# 07_-_INPUT.net
KiCad netlist of a schematic drawn in Altium Designer
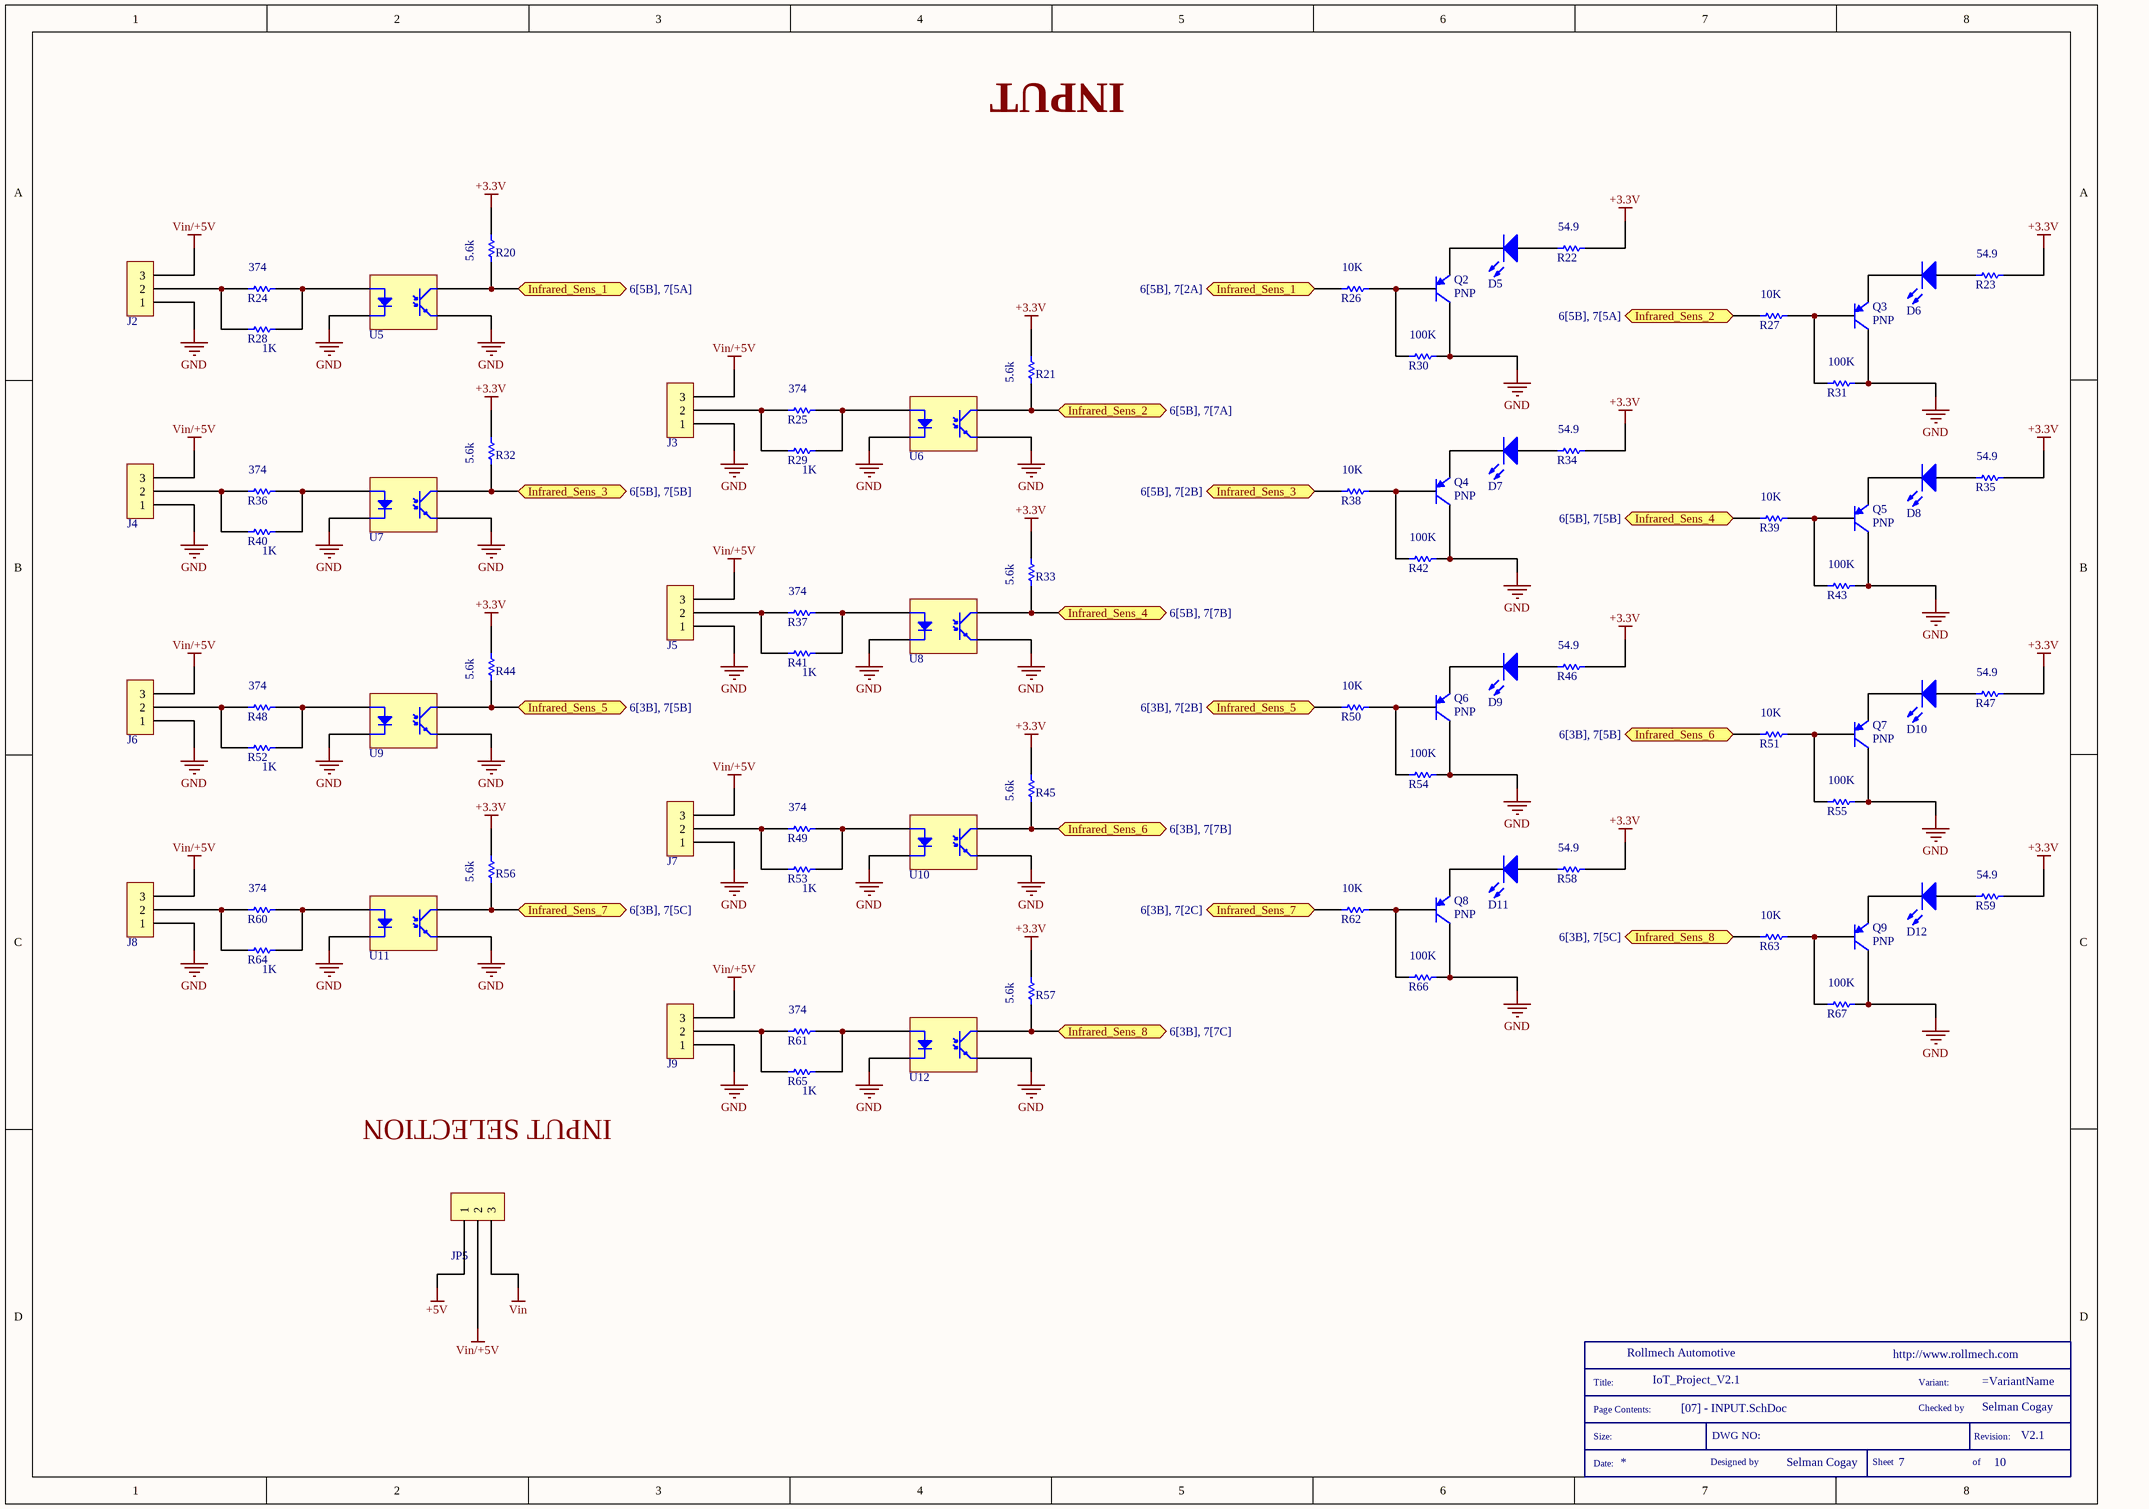
[diagram p0: [07] - INPUT.SchDoc]

(export (version "E")
  (design (tool "Eeschema 10.0.6"))
  (components
    (comp (ref "D5")
      (value "Blue Led")
      (footprint "RES_0603")
      (description "LED BLUE CLEAR 2SMD")
      (libsource (lib "Rollmech_Altium") (part "EAST16084BA8"))
    )
    (comp (ref "D6")
      (value "Blue Led")
      (footprint "RES_0603")
      (description "LED BLUE CLEAR 2SMD")
      (libsource (lib "Rollmech_Altium") (part "EAST16084BA8"))
    )
    (comp (ref "D7")
      (value "Blue Led")
      (footprint "RES_0603")
      (description "LED BLUE CLEAR 2SMD")
      (libsource (lib "Rollmech_Altium") (part "EAST16084BA8"))
    )
    (comp (ref "D8")
      (value "Blue Led")
      (footprint "RES_0603")
      (description "LED BLUE CLEAR 2SMD")
      (libsource (lib "Rollmech_Altium") (part "EAST16084BA8"))
    )
    (comp (ref "D9")
      (value "Blue Led")
      (footprint "RES_0603")
      (description "LED BLUE CLEAR 2SMD")
      (libsource (lib "Rollmech_Altium") (part "EAST16084BA8"))
    )
    (comp (ref "D10")
      (value "Blue Led")
      (footprint "RES_0603")
      (description "LED BLUE CLEAR 2SMD")
      (libsource (lib "Rollmech_Altium") (part "EAST16084BA8"))
    )
    (comp (ref "D11")
      (value "Blue Led")
      (footprint "RES_0603")
      (description "LED BLUE CLEAR 2SMD")
      (libsource (lib "Rollmech_Altium") (part "EAST16084BA8"))
    )
    (comp (ref "D12")
      (value "Blue Led")
      (footprint "RES_0603")
      (description "LED BLUE CLEAR 2SMD")
      (libsource (lib "Rollmech_Altium") (part "EAST16084BA8"))
    )
    (comp (ref "J2")
      (value "CONN 1X3 3MM")
      (footprint "CONN_MALE_1X3_3MM")
      (description "CONN MALE 1X3 3MM")
      (libsource (lib "Rollmech_Altium") (part "66200311122"))
    )
    (comp (ref "J3")
      (value "CONN 1X3 3MM")
      (footprint "CONN_MALE_1X3_3MM")
      (description "CONN MALE 1X3 3MM")
      (libsource (lib "Rollmech_Altium") (part "66200311122"))
    )
    (comp (ref "J4")
      (value "CONN 1X3 3MM")
      (footprint "CONN_MALE_1X3_3MM")
      (description "CONN MALE 1X3 3MM")
      (libsource (lib "Rollmech_Altium") (part "66200311122"))
    )
    (comp (ref "J5")
      (value "CONN 1X3 3MM")
      (footprint "CONN_MALE_1X3_3MM")
      (description "CONN MALE 1X3 3MM")
      (libsource (lib "Rollmech_Altium") (part "66200311122"))
    )
    (comp (ref "J6")
      (value "CONN 1X3 3MM")
      (footprint "CONN_MALE_1X3_3MM")
      (description "CONN MALE 1X3 3MM")
      (libsource (lib "Rollmech_Altium") (part "66200311122"))
    )
    (comp (ref "J7")
      (value "CONN 1X3 3MM")
      (footprint "CONN_MALE_1X3_3MM")
      (description "CONN MALE 1X3 3MM")
      (libsource (lib "Rollmech_Altium") (part "66200311122"))
    )
    (comp (ref "J8")
      (value "CONN 1X3 3MM")
      (footprint "CONN_MALE_1X3_3MM")
      (description "CONN MALE 1X3 3MM")
      (libsource (lib "Rollmech_Altium") (part "66200311122"))
    )
    (comp (ref "J9")
      (value "CONN 1X3 3MM")
      (footprint "CONN_MALE_1X3_3MM")
      (description "CONN MALE 1X3 3MM")
      (libsource (lib "Rollmech_Altium") (part "66200311122"))
    )
    (comp (ref "JP5")
      (value "HDR_1X3_2.54")
      (footprint "HDR_MALE_1X3_2.54MM")
      (description "HDR MALE 1X3 2.54MM")
      (libsource (lib "Rollmech_Altium") (part "61300311121"))
    )
    (comp (ref "Q2")
      (value "PNP")
      (footprint "SOT-23 (TO-236)")
      (description "TRANS PNP 60V 0.6A SOT23-3")
      (libsource (lib "Rollmech_Altium") (part "MMBT2907A-7-F"))
    )
    (comp (ref "Q3")
      (value "PNP")
      (footprint "SOT-23 (TO-236)")
      (description "TRANS PNP 60V 0.6A SOT23-3")
      (libsource (lib "Rollmech_Altium") (part "MMBT2907A-7-F"))
    )
    (comp (ref "Q4")
      (value "PNP")
      (footprint "SOT-23 (TO-236)")
      (description "TRANS PNP 60V 0.6A SOT23-3")
      (libsource (lib "Rollmech_Altium") (part "MMBT2907A-7-F"))
    )
    (comp (ref "Q5")
      (value "PNP")
      (footprint "SOT-23 (TO-236)")
      (description "TRANS PNP 60V 0.6A SOT23-3")
      (libsource (lib "Rollmech_Altium") (part "MMBT2907A-7-F"))
    )
    (comp (ref "Q6")
      (value "PNP")
      (footprint "SOT-23 (TO-236)")
      (description "TRANS PNP 60V 0.6A SOT23-3")
      (libsource (lib "Rollmech_Altium") (part "MMBT2907A-7-F"))
    )
    (comp (ref "Q7")
      (value "PNP")
      (footprint "SOT-23 (TO-236)")
      (description "TRANS PNP 60V 0.6A SOT23-3")
      (libsource (lib "Rollmech_Altium") (part "MMBT2907A-7-F"))
    )
    (comp (ref "Q8")
      (value "PNP")
      (footprint "SOT-23 (TO-236)")
      (description "TRANS PNP 60V 0.6A SOT23-3")
      (libsource (lib "Rollmech_Altium") (part "MMBT2907A-7-F"))
    )
    (comp (ref "Q9")
      (value "PNP")
      (footprint "SOT-23 (TO-236)")
      (description "TRANS PNP 60V 0.6A SOT23-3")
      (libsource (lib "Rollmech_Altium") (part "MMBT2907A-7-F"))
    )
    (comp (ref "R20")
      (value "5.6k")
      (footprint "RES_0805")
      (description "RES SMD 5.6K OHM 1% 1/8W 0805")
      (libsource (lib "Rollmech_Altium") (part "ERJ-6ENF5601V"))
    )
    (comp (ref "R21")
      (value "5.6k")
      (footprint "RES_0805")
      (description "RES SMD 5.6K OHM 1% 1/8W 0805")
      (libsource (lib "Rollmech_Altium") (part "ERJ-6ENF5601V"))
    )
    (comp (ref "R22")
      (value "54.9")
      (footprint "RES_0805")
      (description "RES SMD 54.9 OHM")
      (libsource (lib "Rollmech_Altium") (part "ERJ-6ENF54R9V"))
    )
    (comp (ref "R23")
      (value "54.9")
      (footprint "RES_0805")
      (description "RES SMD 54.9 OHM")
      (libsource (lib "Rollmech_Altium") (part "ERJ-6ENF54R9V"))
    )
    (comp (ref "R24")
      (value "374")
      (footprint "RES_0805")
      (description "RES SMD 374 OHM 1% 1/8W 0805")
      (libsource (lib "Rollmech_Altium") (part "ERJ-6ENF3740V"))
    )
    (comp (ref "R25")
      (value "374")
      (footprint "RES_0805")
      (description "RES SMD 374 OHM 1% 1/8W 0805")
      (libsource (lib "Rollmech_Altium") (part "ERJ-6ENF3740V"))
    )
    (comp (ref "R26")
      (value "10K")
      (footprint "RES_0805")
      (description "RES SMD 10K OHM 1% 1/8W 0805")
      (libsource (lib "Rollmech_Altium") (part "ERJ-6ENF1002V"))
    )
    (comp (ref "R27")
      (value "10K")
      (footprint "RES_0805")
      (description "RES SMD 10K OHM 1% 1/8W 0805")
      (libsource (lib "Rollmech_Altium") (part "ERJ-6ENF1002V"))
    )
    (comp (ref "R28")
      (value "1K")
      (footprint "RES_0805")
      (description "RES SMD 1K OHM")
      (libsource (lib "Rollmech_Altium") (part "ERJ-6ENF1001V"))
    )
    (comp (ref "R29")
      (value "1K")
      (footprint "RES_0805")
      (description "RES SMD 1K OHM")
      (libsource (lib "Rollmech_Altium") (part "ERJ-6ENF1001V"))
    )
    (comp (ref "R30")
      (value "100K")
      (footprint "RES_0603")
      (description "RES SMD 100K 5% 1/4W 0603")
      (libsource (lib "Rollmech_Altium") (part "ERJ-PA3J104V"))
    )
    (comp (ref "R31")
      (value "100K")
      (footprint "RES_0603")
      (description "RES SMD 100K 5% 1/4W 0603")
      (libsource (lib "Rollmech_Altium") (part "ERJ-PA3J104V"))
    )
    (comp (ref "R32")
      (value "5.6k")
      (footprint "RES_0805")
      (description "RES SMD 5.6K OHM 1% 1/8W 0805")
      (libsource (lib "Rollmech_Altium") (part "ERJ-6ENF5601V"))
    )
    (comp (ref "R33")
      (value "5.6k")
      (footprint "RES_0805")
      (description "RES SMD 5.6K OHM 1% 1/8W 0805")
      (libsource (lib "Rollmech_Altium") (part "ERJ-6ENF5601V"))
    )
    (comp (ref "R34")
      (value "54.9")
      (footprint "RES_0805")
      (description "RES SMD 54.9 OHM")
      (libsource (lib "Rollmech_Altium") (part "ERJ-6ENF54R9V"))
    )
    (comp (ref "R35")
      (value "54.9")
      (footprint "RES_0805")
      (description "RES SMD 54.9 OHM")
      (libsource (lib "Rollmech_Altium") (part "ERJ-6ENF54R9V"))
    )
    (comp (ref "R36")
      (value "374")
      (footprint "RES_0805")
      (description "RES SMD 374 OHM 1% 1/8W 0805")
      (libsource (lib "Rollmech_Altium") (part "ERJ-6ENF3740V"))
    )
    (comp (ref "R37")
      (value "374")
      (footprint "RES_0805")
      (description "RES SMD 374 OHM 1% 1/8W 0805")
      (libsource (lib "Rollmech_Altium") (part "ERJ-6ENF3740V"))
    )
    (comp (ref "R38")
      (value "10K")
      (footprint "RES_0805")
      (description "RES SMD 10K OHM 1% 1/8W 0805")
      (libsource (lib "Rollmech_Altium") (part "ERJ-6ENF1002V"))
    )
    (comp (ref "R39")
      (value "10K")
      (footprint "RES_0805")
      (description "RES SMD 10K OHM 1% 1/8W 0805")
      (libsource (lib "Rollmech_Altium") (part "ERJ-6ENF1002V"))
    )
    (comp (ref "R40")
      (value "1K")
      (footprint "RES_0805")
      (description "RES SMD 1K OHM")
      (libsource (lib "Rollmech_Altium") (part "ERJ-6ENF1001V"))
    )
    (comp (ref "R41")
      (value "1K")
      (footprint "RES_0805")
      (description "RES SMD 1K OHM")
      (libsource (lib "Rollmech_Altium") (part "ERJ-6ENF1001V"))
    )
    (comp (ref "R42")
      (value "100K")
      (footprint "RES_0603")
      (description "RES SMD 100K 5% 1/4W 0603")
      (libsource (lib "Rollmech_Altium") (part "ERJ-PA3J104V"))
    )
    (comp (ref "R43")
      (value "100K")
      (footprint "RES_0603")
      (description "RES SMD 100K 5% 1/4W 0603")
      (libsource (lib "Rollmech_Altium") (part "ERJ-PA3J104V"))
    )
    (comp (ref "R44")
      (value "5.6k")
      (footprint "RES_0805")
      (description "RES SMD 5.6K OHM 1% 1/8W 0805")
      (libsource (lib "Rollmech_Altium") (part "ERJ-6ENF5601V"))
    )
    (comp (ref "R45")
      (value "5.6k")
      (footprint "RES_0805")
      (description "RES SMD 5.6K OHM 1% 1/8W 0805")
      (libsource (lib "Rollmech_Altium") (part "ERJ-6ENF5601V"))
    )
    (comp (ref "R46")
      (value "54.9")
      (footprint "RES_0805")
      (description "RES SMD 54.9 OHM")
      (libsource (lib "Rollmech_Altium") (part "ERJ-6ENF54R9V"))
    )
    (comp (ref "R47")
      (value "54.9")
      (footprint "RES_0805")
      (description "RES SMD 54.9 OHM")
      (libsource (lib "Rollmech_Altium") (part "ERJ-6ENF54R9V"))
    )
    (comp (ref "R48")
      (value "374")
      (footprint "RES_0805")
      (description "RES SMD 374 OHM 1% 1/8W 0805")
      (libsource (lib "Rollmech_Altium") (part "ERJ-6ENF3740V"))
    )
    (comp (ref "R49")
      (value "374")
      (footprint "RES_0805")
      (description "RES SMD 374 OHM 1% 1/8W 0805")
      (libsource (lib "Rollmech_Altium") (part "ERJ-6ENF3740V"))
    )
    (comp (ref "R50")
      (value "10K")
      (footprint "RES_0805")
      (description "RES SMD 10K OHM 1% 1/8W 0805")
      (libsource (lib "Rollmech_Altium") (part "ERJ-6ENF1002V"))
    )
    (comp (ref "R51")
      (value "10K")
      (footprint "RES_0805")
      (description "RES SMD 10K OHM 1% 1/8W 0805")
      (libsource (lib "Rollmech_Altium") (part "ERJ-6ENF1002V"))
    )
    (comp (ref "R52")
      (value "1K")
      (footprint "RES_0805")
      (description "RES SMD 1K OHM")
      (libsource (lib "Rollmech_Altium") (part "ERJ-6ENF1001V"))
    )
    (comp (ref "R53")
      (value "1K")
      (footprint "RES_0805")
      (description "RES SMD 1K OHM")
      (libsource (lib "Rollmech_Altium") (part "ERJ-6ENF1001V"))
    )
    (comp (ref "R54")
      (value "100K")
      (footprint "RES_0603")
      (description "RES SMD 100K 5% 1/4W 0603")
      (libsource (lib "Rollmech_Altium") (part "ERJ-PA3J104V"))
    )
    (comp (ref "R55")
      (value "100K")
      (footprint "RES_0603")
      (description "RES SMD 100K 5% 1/4W 0603")
      (libsource (lib "Rollmech_Altium") (part "ERJ-PA3J104V"))
    )
    (comp (ref "R56")
      (value "5.6k")
      (footprint "RES_0805")
      (description "RES SMD 5.6K OHM 1% 1/8W 0805")
      (libsource (lib "Rollmech_Altium") (part "ERJ-6ENF5601V"))
    )
    (comp (ref "R57")
      (value "5.6k")
      (footprint "RES_0805")
      (description "RES SMD 5.6K OHM 1% 1/8W 0805")
      (libsource (lib "Rollmech_Altium") (part "ERJ-6ENF5601V"))
    )
    (comp (ref "R58")
      (value "54.9")
      (footprint "RES_0805")
      (description "RES SMD 54.9 OHM")
      (libsource (lib "Rollmech_Altium") (part "ERJ-6ENF54R9V"))
    )
    (comp (ref "R59")
      (value "54.9")
      (footprint "RES_0805")
      (description "RES SMD 54.9 OHM")
      (libsource (lib "Rollmech_Altium") (part "ERJ-6ENF54R9V"))
    )
    (comp (ref "R60")
      (value "374")
      (footprint "RES_0805")
      (description "RES SMD 374 OHM 1% 1/8W 0805")
      (libsource (lib "Rollmech_Altium") (part "ERJ-6ENF3740V"))
    )
    (comp (ref "R61")
      (value "374")
      (footprint "RES_0805")
      (description "RES SMD 374 OHM 1% 1/8W 0805")
      (libsource (lib "Rollmech_Altium") (part "ERJ-6ENF3740V"))
    )
    (comp (ref "R62")
      (value "10K")
      (footprint "RES_0805")
      (description "RES SMD 10K OHM 1% 1/8W 0805")
      (libsource (lib "Rollmech_Altium") (part "ERJ-6ENF1002V"))
    )
    (comp (ref "R63")
      (value "10K")
      (footprint "RES_0805")
      (description "RES SMD 10K OHM 1% 1/8W 0805")
      (libsource (lib "Rollmech_Altium") (part "ERJ-6ENF1002V"))
    )
    (comp (ref "R64")
      (value "1K")
      (footprint "RES_0805")
      (description "RES SMD 1K OHM")
      (libsource (lib "Rollmech_Altium") (part "ERJ-6ENF1001V"))
    )
    (comp (ref "R65")
      (value "1K")
      (footprint "RES_0805")
      (description "RES SMD 1K OHM")
      (libsource (lib "Rollmech_Altium") (part "ERJ-6ENF1001V"))
    )
    (comp (ref "R66")
      (value "100K")
      (footprint "RES_0603")
      (description "RES SMD 100K 5% 1/4W 0603")
      (libsource (lib "Rollmech_Altium") (part "ERJ-PA3J104V"))
    )
    (comp (ref "R67")
      (value "100K")
      (footprint "RES_0603")
      (description "RES SMD 100K 5% 1/4W 0603")
      (libsource (lib "Rollmech_Altium") (part "ERJ-PA3J104V"))
    )
    (comp (ref "U5")
      (value "NPN 3.75KV")
      (footprint "SOIC-6")
      (description "OPTOISO 3.75KV TRANS")
      (libsource (lib "Rollmech_Altium") (part "TLP2301(TPL,E"))
    )
    (comp (ref "U6")
      (value "NPN 3.75KV")
      (footprint "SOIC-6")
      (description "OPTOISO 3.75KV TRANS")
      (libsource (lib "Rollmech_Altium") (part "TLP2301(TPL,E"))
    )
    (comp (ref "U7")
      (value "NPN 3.75KV")
      (footprint "SOIC-6")
      (description "OPTOISO 3.75KV TRANS")
      (libsource (lib "Rollmech_Altium") (part "TLP2301(TPL,E"))
    )
    (comp (ref "U8")
      (value "NPN 3.75KV")
      (footprint "SOIC-6")
      (description "OPTOISO 3.75KV TRANS")
      (libsource (lib "Rollmech_Altium") (part "TLP2301(TPL,E"))
    )
    (comp (ref "U9")
      (value "NPN 3.75KV")
      (footprint "SOIC-6")
      (description "OPTOISO 3.75KV TRANS")
      (libsource (lib "Rollmech_Altium") (part "TLP2301(TPL,E"))
    )
    (comp (ref "U10")
      (value "NPN 3.75KV")
      (footprint "SOIC-6")
      (description "OPTOISO 3.75KV TRANS")
      (libsource (lib "Rollmech_Altium") (part "TLP2301(TPL,E"))
    )
    (comp (ref "U11")
      (value "NPN 3.75KV")
      (footprint "SOIC-6")
      (description "OPTOISO 3.75KV TRANS")
      (libsource (lib "Rollmech_Altium") (part "TLP2301(TPL,E"))
    )
    (comp (ref "U12")
      (value "NPN 3.75KV")
      (footprint "SOIC-6")
      (description "OPTOISO 3.75KV TRANS")
      (libsource (lib "Rollmech_Altium") (part "TLP2301(TPL,E"))
    )
  )
  (nets
    (net (code "1") (name "+3.3V") (class "Default")
      (node (ref "R20") (pin "2") (pinfunction "2_2") (pintype "passive"))
      (node (ref "R21") (pin "2") (pinfunction "2_2") (pintype "passive"))
      (node (ref "R22") (pin "2") (pinfunction "2_2") (pintype "passive"))
      (node (ref "R23") (pin "2") (pinfunction "2_2") (pintype "passive"))
      (node (ref "R32") (pin "2") (pinfunction "2_2") (pintype "passive"))
      (node (ref "R33") (pin "2") (pinfunction "2_2") (pintype "passive"))
      (node (ref "R34") (pin "2") (pinfunction "2_2") (pintype "passive"))
      (node (ref "R35") (pin "2") (pinfunction "2_2") (pintype "passive"))
      (node (ref "R44") (pin "2") (pinfunction "2_2") (pintype "passive"))
      (node (ref "R45") (pin "2") (pinfunction "2_2") (pintype "passive"))
      (node (ref "R46") (pin "2") (pinfunction "2_2") (pintype "passive"))
      (node (ref "R47") (pin "2") (pinfunction "2_2") (pintype "passive"))
      (node (ref "R56") (pin "2") (pinfunction "2_2") (pintype "passive"))
      (node (ref "R57") (pin "2") (pinfunction "2_2") (pintype "passive"))
      (node (ref "R58") (pin "2") (pinfunction "2_2") (pintype "passive"))
      (node (ref "R59") (pin "2") (pinfunction "2_2") (pintype "passive"))
    )
    (net (code "2") (name "+5V") (class "Default")
      (node (ref "JP5") (pin "1") (pinfunction "1_1") (pintype "passive"))
    )
    (net (code "3") (name "/Infrared_Sens_1") (class "Default")
      (node (ref "R20") (pin "1") (pinfunction "1_1") (pintype "passive"))
      (node (ref "R26") (pin "1") (pinfunction "1_1") (pintype "passive"))
      (node (ref "U5") (pin "6") (pinfunction "Coll_6") (pintype "passive"))
    )
    (net (code "4") (name "/Infrared_Sens_2") (class "Default")
      (node (ref "R21") (pin "1") (pinfunction "1_1") (pintype "passive"))
      (node (ref "R27") (pin "1") (pinfunction "1_1") (pintype "passive"))
      (node (ref "U6") (pin "6") (pinfunction "Coll_6") (pintype "passive"))
    )
    (net (code "5") (name "/Infrared_Sens_3") (class "Default")
      (node (ref "R32") (pin "1") (pinfunction "1_1") (pintype "passive"))
      (node (ref "R38") (pin "1") (pinfunction "1_1") (pintype "passive"))
      (node (ref "U7") (pin "6") (pinfunction "Coll_6") (pintype "passive"))
    )
    (net (code "6") (name "/Infrared_Sens_4") (class "Default")
      (node (ref "R33") (pin "1") (pinfunction "1_1") (pintype "passive"))
      (node (ref "R39") (pin "1") (pinfunction "1_1") (pintype "passive"))
      (node (ref "U8") (pin "6") (pinfunction "Coll_6") (pintype "passive"))
    )
    (net (code "7") (name "/Infrared_Sens_5") (class "Default")
      (node (ref "R44") (pin "1") (pinfunction "1_1") (pintype "passive"))
      (node (ref "R50") (pin "1") (pinfunction "1_1") (pintype "passive"))
      (node (ref "U9") (pin "6") (pinfunction "Coll_6") (pintype "passive"))
    )
    (net (code "8") (name "/Infrared_Sens_6") (class "Default")
      (node (ref "R45") (pin "1") (pinfunction "1_1") (pintype "passive"))
      (node (ref "R51") (pin "1") (pinfunction "1_1") (pintype "passive"))
      (node (ref "U10") (pin "6") (pinfunction "Coll_6") (pintype "passive"))
    )
    (net (code "9") (name "/Infrared_Sens_7") (class "Default")
      (node (ref "R56") (pin "1") (pinfunction "1_1") (pintype "passive"))
      (node (ref "R62") (pin "1") (pinfunction "1_1") (pintype "passive"))
      (node (ref "U11") (pin "6") (pinfunction "Coll_6") (pintype "passive"))
    )
    (net (code "10") (name "/Infrared_Sens_8") (class "Default")
      (node (ref "R57") (pin "1") (pinfunction "1_1") (pintype "passive"))
      (node (ref "R63") (pin "1") (pinfunction "1_1") (pintype "passive"))
      (node (ref "U12") (pin "6") (pinfunction "Coll_6") (pintype "passive"))
    )
    (net (code "11") (name "GND") (class "Default")
      (node (ref "J2") (pin "1") (pinfunction "1_1") (pintype "passive"))
      (node (ref "J3") (pin "1") (pinfunction "1_1") (pintype "passive"))
      (node (ref "J4") (pin "1") (pinfunction "1_1") (pintype "passive"))
      (node (ref "J5") (pin "1") (pinfunction "1_1") (pintype "passive"))
      (node (ref "J6") (pin "1") (pinfunction "1_1") (pintype "passive"))
      (node (ref "J7") (pin "1") (pinfunction "1_1") (pintype "passive"))
      (node (ref "J8") (pin "1") (pinfunction "1_1") (pintype "passive"))
      (node (ref "J9") (pin "1") (pinfunction "1_1") (pintype "passive"))
      (node (ref "Q2") (pin "1") (pinfunction "C_1") (pintype "passive"))
      (node (ref "Q3") (pin "1") (pinfunction "C_1") (pintype "passive"))
      (node (ref "Q4") (pin "1") (pinfunction "C_1") (pintype "passive"))
      (node (ref "Q5") (pin "1") (pinfunction "C_1") (pintype "passive"))
      (node (ref "Q6") (pin "1") (pinfunction "C_1") (pintype "passive"))
      (node (ref "Q7") (pin "1") (pinfunction "C_1") (pintype "passive"))
      (node (ref "Q8") (pin "1") (pinfunction "C_1") (pintype "passive"))
      (node (ref "Q9") (pin "1") (pinfunction "C_1") (pintype "passive"))
      (node (ref "R30") (pin "2") (pinfunction "2_2") (pintype "passive"))
      (node (ref "R31") (pin "2") (pinfunction "2_2") (pintype "passive"))
      (node (ref "R42") (pin "2") (pinfunction "2_2") (pintype "passive"))
      (node (ref "R43") (pin "2") (pinfunction "2_2") (pintype "passive"))
      (node (ref "R54") (pin "2") (pinfunction "2_2") (pintype "passive"))
      (node (ref "R55") (pin "2") (pinfunction "2_2") (pintype "passive"))
      (node (ref "R66") (pin "2") (pinfunction "2_2") (pintype "passive"))
      (node (ref "R67") (pin "2") (pinfunction "2_2") (pintype "passive"))
      (node (ref "U10") (pin "3") (pinfunction "K_3") (pintype "passive"))
      (node (ref "U10") (pin "4") (pinfunction "Emit_4") (pintype "passive"))
      (node (ref "U11") (pin "3") (pinfunction "K_3") (pintype "passive"))
      (node (ref "U11") (pin "4") (pinfunction "Emit_4") (pintype "passive"))
      (node (ref "U12") (pin "3") (pinfunction "K_3") (pintype "passive"))
      (node (ref "U12") (pin "4") (pinfunction "Emit_4") (pintype "passive"))
      (node (ref "U5") (pin "3") (pinfunction "K_3") (pintype "passive"))
      (node (ref "U5") (pin "4") (pinfunction "Emit_4") (pintype "passive"))
      (node (ref "U6") (pin "3") (pinfunction "K_3") (pintype "passive"))
      (node (ref "U6") (pin "4") (pinfunction "Emit_4") (pintype "passive"))
      (node (ref "U7") (pin "3") (pinfunction "K_3") (pintype "passive"))
      (node (ref "U7") (pin "4") (pinfunction "Emit_4") (pintype "passive"))
      (node (ref "U8") (pin "3") (pinfunction "K_3") (pintype "passive"))
      (node (ref "U8") (pin "4") (pinfunction "Emit_4") (pintype "passive"))
      (node (ref "U9") (pin "3") (pinfunction "K_3") (pintype "passive"))
      (node (ref "U9") (pin "4") (pinfunction "Emit_4") (pintype "passive"))
    )
    (net (code "12") (name "Net-(D5-A)") (class "Default")
      (node (ref "D5") (pin "1") (pinfunction "A_1") (pintype "passive"))
      (node (ref "R22") (pin "1") (pinfunction "1_1") (pintype "passive"))
    )
    (net (code "13") (name "Net-(D5-K)") (class "Default")
      (node (ref "D5") (pin "2") (pinfunction "K_2") (pintype "passive"))
      (node (ref "Q2") (pin "3") (pinfunction "E_3") (pintype "passive"))
    )
    (net (code "14") (name "Net-(D6-A)") (class "Default")
      (node (ref "D6") (pin "1") (pinfunction "A_1") (pintype "passive"))
      (node (ref "R23") (pin "1") (pinfunction "1_1") (pintype "passive"))
    )
    (net (code "15") (name "Net-(D6-K)") (class "Default")
      (node (ref "D6") (pin "2") (pinfunction "K_2") (pintype "passive"))
      (node (ref "Q3") (pin "3") (pinfunction "E_3") (pintype "passive"))
    )
    (net (code "16") (name "Net-(D7-A)") (class "Default")
      (node (ref "D7") (pin "1") (pinfunction "A_1") (pintype "passive"))
      (node (ref "R34") (pin "1") (pinfunction "1_1") (pintype "passive"))
    )
    (net (code "17") (name "Net-(D7-K)") (class "Default")
      (node (ref "D7") (pin "2") (pinfunction "K_2") (pintype "passive"))
      (node (ref "Q4") (pin "3") (pinfunction "E_3") (pintype "passive"))
    )
    (net (code "18") (name "Net-(D8-A)") (class "Default")
      (node (ref "D8") (pin "1") (pinfunction "A_1") (pintype "passive"))
      (node (ref "R35") (pin "1") (pinfunction "1_1") (pintype "passive"))
    )
    (net (code "19") (name "Net-(D8-K)") (class "Default")
      (node (ref "D8") (pin "2") (pinfunction "K_2") (pintype "passive"))
      (node (ref "Q5") (pin "3") (pinfunction "E_3") (pintype "passive"))
    )
    (net (code "20") (name "Net-(D9-A)") (class "Default")
      (node (ref "D9") (pin "1") (pinfunction "A_1") (pintype "passive"))
      (node (ref "R46") (pin "1") (pinfunction "1_1") (pintype "passive"))
    )
    (net (code "21") (name "Net-(D9-K)") (class "Default")
      (node (ref "D9") (pin "2") (pinfunction "K_2") (pintype "passive"))
      (node (ref "Q6") (pin "3") (pinfunction "E_3") (pintype "passive"))
    )
    (net (code "22") (name "Net-(D10-A)") (class "Default")
      (node (ref "D10") (pin "1") (pinfunction "A_1") (pintype "passive"))
      (node (ref "R47") (pin "1") (pinfunction "1_1") (pintype "passive"))
    )
    (net (code "23") (name "Net-(D10-K)") (class "Default")
      (node (ref "D10") (pin "2") (pinfunction "K_2") (pintype "passive"))
      (node (ref "Q7") (pin "3") (pinfunction "E_3") (pintype "passive"))
    )
    (net (code "24") (name "Net-(D11-A)") (class "Default")
      (node (ref "D11") (pin "1") (pinfunction "A_1") (pintype "passive"))
      (node (ref "R58") (pin "1") (pinfunction "1_1") (pintype "passive"))
    )
    (net (code "25") (name "Net-(D11-K)") (class "Default")
      (node (ref "D11") (pin "2") (pinfunction "K_2") (pintype "passive"))
      (node (ref "Q8") (pin "3") (pinfunction "E_3") (pintype "passive"))
    )
    (net (code "26") (name "Net-(D12-A)") (class "Default")
      (node (ref "D12") (pin "1") (pinfunction "A_1") (pintype "passive"))
      (node (ref "R59") (pin "1") (pinfunction "1_1") (pintype "passive"))
    )
    (net (code "27") (name "Net-(D12-K)") (class "Default")
      (node (ref "D12") (pin "2") (pinfunction "K_2") (pintype "passive"))
      (node (ref "Q9") (pin "3") (pinfunction "E_3") (pintype "passive"))
    )
    (net (code "28") (name "Net-(J2-Pad2)") (class "Default")
      (node (ref "J2") (pin "2") (pinfunction "2_2") (pintype "passive"))
      (node (ref "R24") (pin "1") (pinfunction "1_1") (pintype "passive"))
      (node (ref "R28") (pin "1") (pinfunction "1_1") (pintype "passive"))
    )
    (net (code "29") (name "Net-(J3-Pad2)") (class "Default")
      (node (ref "J3") (pin "2") (pinfunction "2_2") (pintype "passive"))
      (node (ref "R25") (pin "1") (pinfunction "1_1") (pintype "passive"))
      (node (ref "R29") (pin "1") (pinfunction "1_1") (pintype "passive"))
    )
    (net (code "30") (name "Net-(J4-Pad2)") (class "Default")
      (node (ref "J4") (pin "2") (pinfunction "2_2") (pintype "passive"))
      (node (ref "R36") (pin "1") (pinfunction "1_1") (pintype "passive"))
      (node (ref "R40") (pin "1") (pinfunction "1_1") (pintype "passive"))
    )
    (net (code "31") (name "Net-(J5-Pad2)") (class "Default")
      (node (ref "J5") (pin "2") (pinfunction "2_2") (pintype "passive"))
      (node (ref "R37") (pin "1") (pinfunction "1_1") (pintype "passive"))
      (node (ref "R41") (pin "1") (pinfunction "1_1") (pintype "passive"))
    )
    (net (code "32") (name "Net-(J6-Pad2)") (class "Default")
      (node (ref "J6") (pin "2") (pinfunction "2_2") (pintype "passive"))
      (node (ref "R48") (pin "1") (pinfunction "1_1") (pintype "passive"))
      (node (ref "R52") (pin "1") (pinfunction "1_1") (pintype "passive"))
    )
    (net (code "33") (name "Net-(J7-Pad2)") (class "Default")
      (node (ref "J7") (pin "2") (pinfunction "2_2") (pintype "passive"))
      (node (ref "R49") (pin "1") (pinfunction "1_1") (pintype "passive"))
      (node (ref "R53") (pin "1") (pinfunction "1_1") (pintype "passive"))
    )
    (net (code "34") (name "Net-(J8-Pad2)") (class "Default")
      (node (ref "J8") (pin "2") (pinfunction "2_2") (pintype "passive"))
      (node (ref "R60") (pin "1") (pinfunction "1_1") (pintype "passive"))
      (node (ref "R64") (pin "1") (pinfunction "1_1") (pintype "passive"))
    )
    (net (code "35") (name "Net-(J9-Pad2)") (class "Default")
      (node (ref "J9") (pin "2") (pinfunction "2_2") (pintype "passive"))
      (node (ref "R61") (pin "1") (pinfunction "1_1") (pintype "passive"))
      (node (ref "R65") (pin "1") (pinfunction "1_1") (pintype "passive"))
    )
    (net (code "36") (name "Net-(Q2-B)") (class "Default")
      (node (ref "Q2") (pin "2") (pinfunction "B_2") (pintype "passive"))
      (node (ref "R26") (pin "2") (pinfunction "2_2") (pintype "passive"))
      (node (ref "R30") (pin "1") (pinfunction "1_1") (pintype "passive"))
    )
    (net (code "37") (name "Net-(Q3-B)") (class "Default")
      (node (ref "Q3") (pin "2") (pinfunction "B_2") (pintype "passive"))
      (node (ref "R27") (pin "2") (pinfunction "2_2") (pintype "passive"))
      (node (ref "R31") (pin "1") (pinfunction "1_1") (pintype "passive"))
    )
    (net (code "38") (name "Net-(Q4-B)") (class "Default")
      (node (ref "Q4") (pin "2") (pinfunction "B_2") (pintype "passive"))
      (node (ref "R38") (pin "2") (pinfunction "2_2") (pintype "passive"))
      (node (ref "R42") (pin "1") (pinfunction "1_1") (pintype "passive"))
    )
    (net (code "39") (name "Net-(Q5-B)") (class "Default")
      (node (ref "Q5") (pin "2") (pinfunction "B_2") (pintype "passive"))
      (node (ref "R39") (pin "2") (pinfunction "2_2") (pintype "passive"))
      (node (ref "R43") (pin "1") (pinfunction "1_1") (pintype "passive"))
    )
    (net (code "40") (name "Net-(Q6-B)") (class "Default")
      (node (ref "Q6") (pin "2") (pinfunction "B_2") (pintype "passive"))
      (node (ref "R50") (pin "2") (pinfunction "2_2") (pintype "passive"))
      (node (ref "R54") (pin "1") (pinfunction "1_1") (pintype "passive"))
    )
    (net (code "41") (name "Net-(Q7-B)") (class "Default")
      (node (ref "Q7") (pin "2") (pinfunction "B_2") (pintype "passive"))
      (node (ref "R51") (pin "2") (pinfunction "2_2") (pintype "passive"))
      (node (ref "R55") (pin "1") (pinfunction "1_1") (pintype "passive"))
    )
    (net (code "42") (name "Net-(Q8-B)") (class "Default")
      (node (ref "Q8") (pin "2") (pinfunction "B_2") (pintype "passive"))
      (node (ref "R62") (pin "2") (pinfunction "2_2") (pintype "passive"))
      (node (ref "R66") (pin "1") (pinfunction "1_1") (pintype "passive"))
    )
    (net (code "43") (name "Net-(Q9-B)") (class "Default")
      (node (ref "Q9") (pin "2") (pinfunction "B_2") (pintype "passive"))
      (node (ref "R63") (pin "2") (pinfunction "2_2") (pintype "passive"))
      (node (ref "R67") (pin "1") (pinfunction "1_1") (pintype "passive"))
    )
    (net (code "44") (name "Net-(U5-A)") (class "Default")
      (node (ref "R24") (pin "2") (pinfunction "2_2") (pintype "passive"))
      (node (ref "R28") (pin "2") (pinfunction "2_2") (pintype "passive"))
      (node (ref "U5") (pin "1") (pinfunction "A_1") (pintype "passive"))
    )
    (net (code "45") (name "Net-(U6-A)") (class "Default")
      (node (ref "R25") (pin "2") (pinfunction "2_2") (pintype "passive"))
      (node (ref "R29") (pin "2") (pinfunction "2_2") (pintype "passive"))
      (node (ref "U6") (pin "1") (pinfunction "A_1") (pintype "passive"))
    )
    (net (code "46") (name "Net-(U7-A)") (class "Default")
      (node (ref "R36") (pin "2") (pinfunction "2_2") (pintype "passive"))
      (node (ref "R40") (pin "2") (pinfunction "2_2") (pintype "passive"))
      (node (ref "U7") (pin "1") (pinfunction "A_1") (pintype "passive"))
    )
    (net (code "47") (name "Net-(U8-A)") (class "Default")
      (node (ref "R37") (pin "2") (pinfunction "2_2") (pintype "passive"))
      (node (ref "R41") (pin "2") (pinfunction "2_2") (pintype "passive"))
      (node (ref "U8") (pin "1") (pinfunction "A_1") (pintype "passive"))
    )
    (net (code "48") (name "Net-(U9-A)") (class "Default")
      (node (ref "R48") (pin "2") (pinfunction "2_2") (pintype "passive"))
      (node (ref "R52") (pin "2") (pinfunction "2_2") (pintype "passive"))
      (node (ref "U9") (pin "1") (pinfunction "A_1") (pintype "passive"))
    )
    (net (code "49") (name "Net-(U10-A)") (class "Default")
      (node (ref "R49") (pin "2") (pinfunction "2_2") (pintype "passive"))
      (node (ref "R53") (pin "2") (pinfunction "2_2") (pintype "passive"))
      (node (ref "U10") (pin "1") (pinfunction "A_1") (pintype "passive"))
    )
    (net (code "50") (name "Net-(U11-A)") (class "Default")
      (node (ref "R60") (pin "2") (pinfunction "2_2") (pintype "passive"))
      (node (ref "R64") (pin "2") (pinfunction "2_2") (pintype "passive"))
      (node (ref "U11") (pin "1") (pinfunction "A_1") (pintype "passive"))
    )
    (net (code "51") (name "Net-(U12-A)") (class "Default")
      (node (ref "R61") (pin "2") (pinfunction "2_2") (pintype "passive"))
      (node (ref "R65") (pin "2") (pinfunction "2_2") (pintype "passive"))
      (node (ref "U12") (pin "1") (pinfunction "A_1") (pintype "passive"))
    )
    (net (code "52") (name "Vin") (class "Default")
      (node (ref "JP5") (pin "3") (pinfunction "3_3") (pintype "passive"))
    )
    (net (code "53") (name "Vin{slash}+5V") (class "Default")
      (node (ref "J2") (pin "3") (pinfunction "3_3") (pintype "passive"))
      (node (ref "J3") (pin "3") (pinfunction "3_3") (pintype "passive"))
      (node (ref "J4") (pin "3") (pinfunction "3_3") (pintype "passive"))
      (node (ref "J5") (pin "3") (pinfunction "3_3") (pintype "passive"))
      (node (ref "J6") (pin "3") (pinfunction "3_3") (pintype "passive"))
      (node (ref "J7") (pin "3") (pinfunction "3_3") (pintype "passive"))
      (node (ref "J8") (pin "3") (pinfunction "3_3") (pintype "passive"))
      (node (ref "J9") (pin "3") (pinfunction "3_3") (pintype "passive"))
      (node (ref "JP5") (pin "2") (pinfunction "2_2") (pintype "passive"))
    )
  )
)
